# controller_pcb.net
KiCad netlist of a schematic drawn in EAGLE
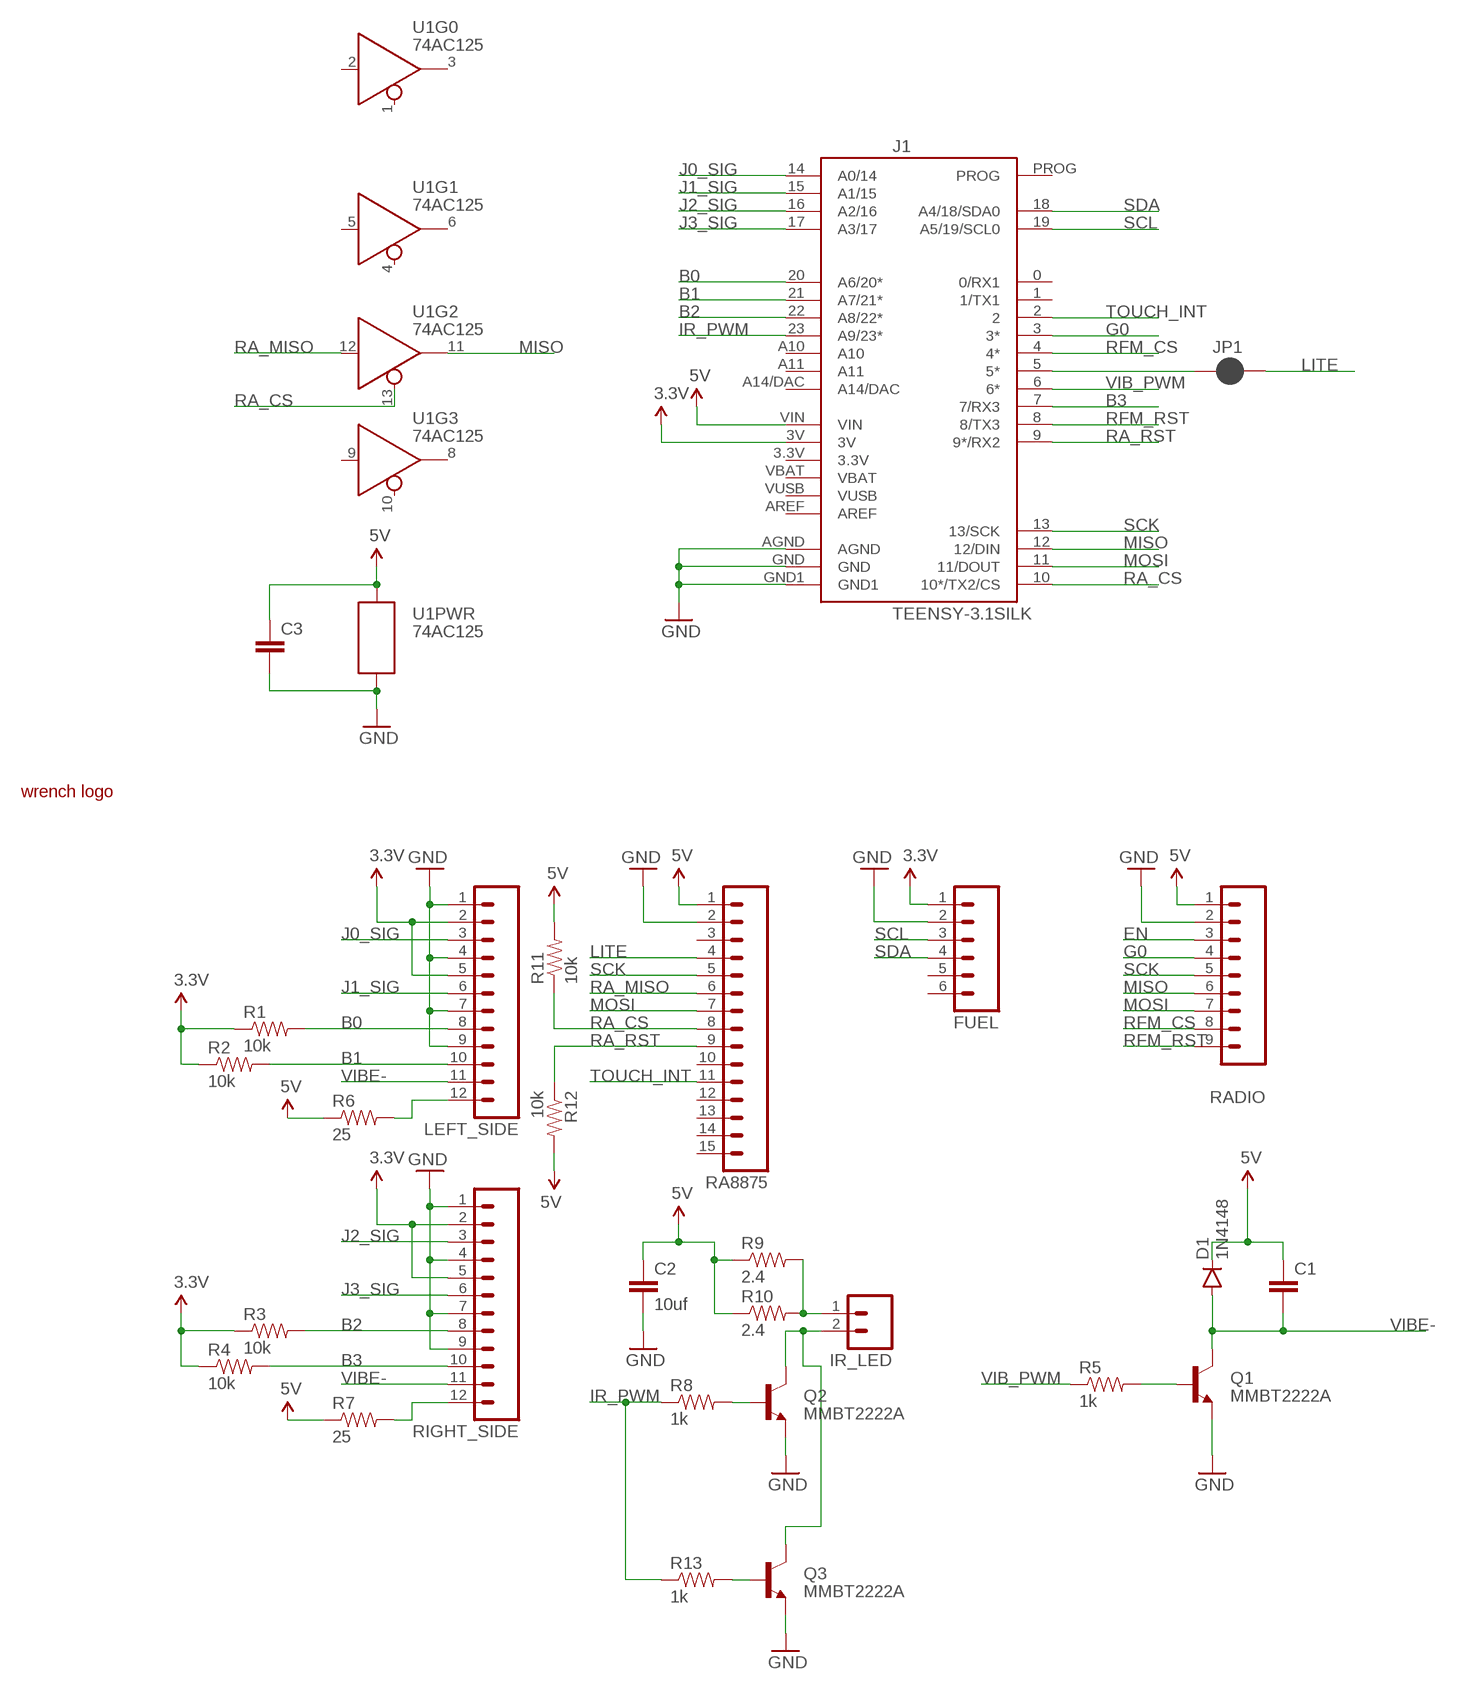
[diagram p0: schematic, sheet 1]

(export (version "E")
  (design (tool "Eeschema 10.0.6"))
  (components
    (comp (ref "C1")
      (value "CAP0805")
      (footprint "eagle-import:0805")
      (libsource (lib "eagle-import") (part "CAP0805"))
    )
    (comp (ref "C2")
      (value "10uf")
      (footprint "eagle-import:1206")
      (libsource (lib "eagle-import") (part "CAP1206"))
    )
    (comp (ref "C3")
      (value "CAP0805")
      (footprint "eagle-import:0805")
      (libsource (lib "eagle-import") (part "CAP0805"))
    )
    (comp (ref "D1")
      (value "1N4148")
      (footprint "eagle-import:DIODE-1N4148")
      (libsource (lib "eagle-import") (part "DIODE1N4148"))
    )
    (comp (ref "FUEL")
      (value "M06LOCK_LONGPADS")
      (footprint "eagle-import:1X06_LOCK_LONGPADS")
      (libsource (lib "eagle-import") (part "M06LOCK_LONGPADS"))
    )
    (comp (ref "IR_LED")
      (value "M02PTH3")
      (footprint "eagle-import:1X02_LONGPADS")
      (libsource (lib "eagle-import") (part "M02PTH3"))
    )
    (comp (ref "J1")
      (value "TEENSY-3.1SILK")
      (footprint "eagle-import:TEENSY-3.1")
      (libsource (lib "eagle-import") (part "TEENSY-3.1SILK"))
    )
    (comp (ref "JP1")
      (value "JUMPER-PAD-2-NC_BY_PASTE")
      (footprint "eagle-import:PAD-JUMPER-2-NC_BY_PASTE_YES_SILK")
      (libsource (lib "eagle-import") (part "JUMPER-PAD-2-NC_BY_PASTE"))
    )
    (comp (ref "LEFT_SIDE")
      (value "M12LONGPADS")
      (footprint "eagle-import:1X12_LONGPADS")
      (libsource (lib "eagle-import") (part "M12LONGPADS"))
    )
    (comp (ref "Q1")
      (value "MMBT2222A")
      (footprint "eagle-import:SOT23-3")
      (libsource (lib "eagle-import") (part "TRANSISTOR_NPNMMBT2222A"))
    )
    (comp (ref "Q2")
      (value "MMBT2222A")
      (footprint "eagle-import:SOT23-3")
      (libsource (lib "eagle-import") (part "TRANSISTOR_NPNMMBT2222A"))
    )
    (comp (ref "Q3")
      (value "MMBT2222A")
      (footprint "eagle-import:SOT23-3")
      (libsource (lib "eagle-import") (part "TRANSISTOR_NPNMMBT2222A"))
    )
    (comp (ref "R1")
      (value "10k")
      (footprint "eagle-import:0805")
      (libsource (lib "eagle-import") (part "RESISTOR0805-RES"))
    )
    (comp (ref "R2")
      (value "10k")
      (footprint "eagle-import:0805")
      (libsource (lib "eagle-import") (part "RESISTOR0805-RES"))
    )
    (comp (ref "R3")
      (value "10k")
      (footprint "eagle-import:0805")
      (libsource (lib "eagle-import") (part "RESISTOR0805-RES"))
    )
    (comp (ref "R4")
      (value "10k")
      (footprint "eagle-import:0805")
      (libsource (lib "eagle-import") (part "RESISTOR0805-RES"))
    )
    (comp (ref "R5")
      (value "1k")
      (footprint "eagle-import:0805")
      (libsource (lib "eagle-import") (part "RESISTOR0805-RES"))
    )
    (comp (ref "R6")
      (value "25")
      (footprint "eagle-import:0805")
      (libsource (lib "eagle-import") (part "RESISTOR0805-RES"))
    )
    (comp (ref "R7")
      (value "25")
      (footprint "eagle-import:0805")
      (libsource (lib "eagle-import") (part "RESISTOR0805-RES"))
    )
    (comp (ref "R8")
      (value "1k")
      (footprint "eagle-import:0805")
      (libsource (lib "eagle-import") (part "RESISTOR0805-RES"))
    )
    (comp (ref "R9")
      (value "2.4")
      (footprint "eagle-import:AXIAL-0.5")
      (libsource (lib "eagle-import") (part "RESISTORPTH-1/2W"))
    )
    (comp (ref "R10")
      (value "2.4")
      (footprint "eagle-import:AXIAL-0.5")
      (libsource (lib "eagle-import") (part "RESISTORPTH-1/2W"))
    )
    (comp (ref "R11")
      (value "10k")
      (footprint "eagle-import:0805")
      (libsource (lib "eagle-import") (part "RESISTOR0805-RES"))
    )
    (comp (ref "R12")
      (value "10k")
      (footprint "eagle-import:0805")
      (libsource (lib "eagle-import") (part "RESISTOR0805-RES"))
    )
    (comp (ref "R13")
      (value "1k")
      (footprint "eagle-import:0805")
      (libsource (lib "eagle-import") (part "RESISTOR0805-RES"))
    )
    (comp (ref "RA8875")
      (value "M15LOCK_LONGPADS")
      (footprint "eagle-import:1X15_LOCK_LONGPADS")
      (libsource (lib "eagle-import") (part "M15LOCK_LONGPADS"))
    )
    (comp (ref "RADIO")
      (value "M09LOCK-LONGPADS")
      (footprint "eagle-import:1X09_LOCK_LONGPADS")
      (libsource (lib "eagle-import") (part "M09LOCK-LONGPADS"))
    )
    (comp (ref "RIGHT_SIDE")
      (value "M12LONGPADS")
      (footprint "eagle-import:1X12_LONGPADS")
      (libsource (lib "eagle-import") (part "M12LONGPADS"))
    )
    (comp (ref "U$1")
      (value "SMALL")
      (footprint "eagle-import:WRENCHLOGO")
      (libsource (lib "eagle-import") (part "SMALL"))
    )
    (comp (ref "U1")
      (value "74AC125")
      (footprint "eagle-import:SO14")
      (libsource (lib "eagle-import") (part "74125AC125DG"))
    )
  )
  (nets
    (net (code "1") (name "/B0") (class "Default")
      (node (ref "J1") (pin "20") (pinfunction "A6/20*_20") (pintype "bidirectional"))
      (node (ref "LEFT_SIDE") (pin "8") (pinfunction "8_8") (pintype "passive"))
      (node (ref "R1") (pin "2") (pinfunction "2_2") (pintype "passive"))
    )
    (net (code "2") (name "/B1") (class "Default")
      (node (ref "J1") (pin "21") (pinfunction "A7/21*_21") (pintype "bidirectional"))
      (node (ref "LEFT_SIDE") (pin "10") (pinfunction "10_10") (pintype "passive"))
      (node (ref "R2") (pin "2") (pinfunction "2_2") (pintype "passive"))
    )
    (net (code "3") (name "/B2") (class "Default")
      (node (ref "J1") (pin "22") (pinfunction "A8/22*_22") (pintype "bidirectional"))
      (node (ref "R3") (pin "2") (pinfunction "2_2") (pintype "passive"))
      (node (ref "RIGHT_SIDE") (pin "8") (pinfunction "8_8") (pintype "passive"))
    )
    (net (code "4") (name "/B3") (class "Default")
      (node (ref "J1") (pin "7") (pinfunction "7/RX3_7") (pintype "bidirectional"))
      (node (ref "R4") (pin "2") (pinfunction "2_2") (pintype "passive"))
      (node (ref "RIGHT_SIDE") (pin "10") (pinfunction "10_10") (pintype "passive"))
    )
    (net (code "5") (name "/EN") (class "Default")
      (node (ref "RADIO") (pin "3") (pinfunction "3_3") (pintype "passive"))
    )
    (net (code "6") (name "/G0") (class "Default")
      (node (ref "J1") (pin "3") (pinfunction "3*_3") (pintype "bidirectional"))
      (node (ref "RADIO") (pin "4") (pinfunction "4_4") (pintype "passive"))
    )
    (net (code "7") (name "/IR_PWM") (class "Default")
      (node (ref "J1") (pin "23") (pinfunction "A9/23*_23") (pintype "bidirectional"))
      (node (ref "R13") (pin "1") (pinfunction "1_1") (pintype "passive"))
      (node (ref "R8") (pin "1") (pinfunction "1_1") (pintype "passive"))
    )
    (net (code "8") (name "/J0_SIG") (class "Default")
      (node (ref "J1") (pin "14") (pinfunction "A0/14_14") (pintype "bidirectional"))
      (node (ref "LEFT_SIDE") (pin "3") (pinfunction "3_3") (pintype "passive"))
    )
    (net (code "9") (name "/J1_SIG") (class "Default")
      (node (ref "J1") (pin "15") (pinfunction "A1/15_15") (pintype "bidirectional"))
      (node (ref "LEFT_SIDE") (pin "6") (pinfunction "6_6") (pintype "passive"))
    )
    (net (code "10") (name "/J2_SIG") (class "Default")
      (node (ref "J1") (pin "16") (pinfunction "A2/16_16") (pintype "bidirectional"))
      (node (ref "RIGHT_SIDE") (pin "3") (pinfunction "3_3") (pintype "passive"))
    )
    (net (code "11") (name "/J3_SIG") (class "Default")
      (node (ref "J1") (pin "17") (pinfunction "A3/17_17") (pintype "bidirectional"))
      (node (ref "RIGHT_SIDE") (pin "6") (pinfunction "6_6") (pintype "passive"))
    )
    (net (code "12") (name "/LITE") (class "Default")
      (node (ref "JP1") (pin "2") (pinfunction "2_2") (pintype "passive"))
      (node (ref "RA8875") (pin "4") (pinfunction "4_4") (pintype "passive"))
    )
    (net (code "13") (name "/MISO") (class "Default")
      (node (ref "J1") (pin "12") (pinfunction "12/DIN_12") (pintype "bidirectional"))
      (node (ref "RADIO") (pin "6") (pinfunction "6_6") (pintype "passive"))
      (node (ref "U1") (pin "11") (pinfunction "Q_11") (pintype "bidirectional"))
    )
    (net (code "14") (name "/MOSI") (class "Default")
      (node (ref "J1") (pin "11") (pinfunction "11/DOUT_11") (pintype "bidirectional"))
      (node (ref "RA8875") (pin "7") (pinfunction "7_7") (pintype "passive"))
      (node (ref "RADIO") (pin "7") (pinfunction "7_7") (pintype "passive"))
    )
    (net (code "15") (name "/RA_CS") (class "Default")
      (node (ref "J1") (pin "10") (pinfunction "10*/TX2/CS_10") (pintype "bidirectional"))
      (node (ref "R11") (pin "1") (pinfunction "1_1") (pintype "passive"))
      (node (ref "RA8875") (pin "8") (pinfunction "8_8") (pintype "passive"))
      (node (ref "U1") (pin "13") (pinfunction "~{EN}_13") (pintype "bidirectional"))
    )
    (net (code "16") (name "/RA_MISO") (class "Default")
      (node (ref "RA8875") (pin "6") (pinfunction "6_6") (pintype "passive"))
      (node (ref "U1") (pin "12") (pinfunction "D_12") (pintype "bidirectional"))
    )
    (net (code "17") (name "/RA_RST") (class "Default")
      (node (ref "J1") (pin "9") (pinfunction "9*/RX2_9") (pintype "bidirectional"))
      (node (ref "R12") (pin "1") (pinfunction "1_1") (pintype "passive"))
      (node (ref "RA8875") (pin "9") (pinfunction "9_9") (pintype "passive"))
    )
    (net (code "18") (name "/RFM_CS") (class "Default")
      (node (ref "J1") (pin "4") (pinfunction "4*_4") (pintype "bidirectional"))
      (node (ref "RADIO") (pin "8") (pinfunction "8_8") (pintype "passive"))
    )
    (net (code "19") (name "/RFM_RST") (class "Default")
      (node (ref "J1") (pin "8") (pinfunction "8/TX3_8") (pintype "bidirectional"))
      (node (ref "RADIO") (pin "9") (pinfunction "9_9") (pintype "passive"))
    )
    (net (code "20") (name "/SCK") (class "Default")
      (node (ref "J1") (pin "13") (pinfunction "13/SCK_13") (pintype "bidirectional"))
      (node (ref "RA8875") (pin "5") (pinfunction "5_5") (pintype "passive"))
      (node (ref "RADIO") (pin "5") (pinfunction "5_5") (pintype "passive"))
    )
    (net (code "21") (name "/SCL") (class "Default")
      (node (ref "FUEL") (pin "3") (pinfunction "3_3") (pintype "passive"))
      (node (ref "J1") (pin "19") (pinfunction "A5/19/SCL0_19") (pintype "bidirectional"))
    )
    (net (code "22") (name "/SDA") (class "Default")
      (node (ref "FUEL") (pin "4") (pinfunction "4_4") (pintype "passive"))
      (node (ref "J1") (pin "18") (pinfunction "A4/18/SDA0_18") (pintype "bidirectional"))
    )
    (net (code "23") (name "/TOUCH_INT") (class "Default")
      (node (ref "J1") (pin "2") (pinfunction "2_2") (pintype "bidirectional"))
      (node (ref "RA8875") (pin "11") (pinfunction "11_11") (pintype "passive"))
    )
    (net (code "24") (name "/VIBE-") (class "Default")
      (node (ref "C1") (pin "2") (pinfunction "2_2") (pintype "passive"))
      (node (ref "D1") (pin "A") (pinfunction "A_A") (pintype "passive"))
      (node (ref "LEFT_SIDE") (pin "11") (pinfunction "11_11") (pintype "passive"))
      (node (ref "Q1") (pin "3") (pinfunction "C_3") (pintype "passive"))
      (node (ref "RIGHT_SIDE") (pin "11") (pinfunction "11_11") (pintype "passive"))
    )
    (net (code "25") (name "/VIB_PWM") (class "Default")
      (node (ref "J1") (pin "6") (pinfunction "6*_6") (pintype "bidirectional"))
      (node (ref "R5") (pin "1") (pinfunction "1_1") (pintype "passive"))
    )
    (net (code "26") (name "3.3V") (class "Default")
      (node (ref "FUEL") (pin "1") (pinfunction "1_1") (pintype "passive"))
      (node (ref "J1") (pin "3V") (pinfunction "3V_3V") (pintype "bidirectional"))
      (node (ref "LEFT_SIDE") (pin "2") (pinfunction "2_2") (pintype "passive"))
      (node (ref "LEFT_SIDE") (pin "5") (pinfunction "5_5") (pintype "passive"))
      (node (ref "R1") (pin "1") (pinfunction "1_1") (pintype "passive"))
      (node (ref "R2") (pin "1") (pinfunction "1_1") (pintype "passive"))
      (node (ref "R3") (pin "1") (pinfunction "1_1") (pintype "passive"))
      (node (ref "R4") (pin "1") (pinfunction "1_1") (pintype "passive"))
      (node (ref "RIGHT_SIDE") (pin "2") (pinfunction "2_2") (pintype "passive"))
      (node (ref "RIGHT_SIDE") (pin "5") (pinfunction "5_5") (pintype "passive"))
    )
    (net (code "27") (name "5V") (class "Default")
      (node (ref "C1") (pin "1") (pinfunction "1_1") (pintype "passive"))
      (node (ref "C2") (pin "1") (pinfunction "1_1") (pintype "passive"))
      (node (ref "C3") (pin "1") (pinfunction "1_1") (pintype "passive"))
      (node (ref "D1") (pin "C") (pinfunction "C_C") (pintype "passive"))
      (node (ref "J1") (pin "VIN") (pinfunction "VIN_VIN") (pintype "bidirectional"))
      (node (ref "R10") (pin "P$1") (pinfunction "1_P$1") (pintype "passive"))
      (node (ref "R11") (pin "2") (pinfunction "2_2") (pintype "passive"))
      (node (ref "R12") (pin "2") (pinfunction "2_2") (pintype "passive"))
      (node (ref "R6") (pin "1") (pinfunction "1_1") (pintype "passive"))
      (node (ref "R7") (pin "1") (pinfunction "1_1") (pintype "passive"))
      (node (ref "R9") (pin "P$1") (pinfunction "1_P$1") (pintype "passive"))
      (node (ref "RA8875") (pin "1") (pinfunction "1_1") (pintype "passive"))
      (node (ref "RADIO") (pin "1") (pinfunction "1_1") (pintype "passive"))
      (node (ref "U1") (pin "14") (pinfunction "P$V+_14") (pintype "bidirectional"))
    )
    (net (code "28") (name "GND") (class "Default")
      (node (ref "C2") (pin "2") (pinfunction "2_2") (pintype "passive"))
      (node (ref "C3") (pin "2") (pinfunction "2_2") (pintype "passive"))
      (node (ref "FUEL") (pin "2") (pinfunction "2_2") (pintype "passive"))
      (node (ref "J1") (pin "AGND") (pinfunction "AGND_AGND") (pintype "bidirectional"))
      (node (ref "J1") (pin "GND") (pinfunction "GND_GND") (pintype "bidirectional"))
      (node (ref "J1") (pin "GND1") (pinfunction "GND1_GND1") (pintype "bidirectional"))
      (node (ref "LEFT_SIDE") (pin "1") (pinfunction "1_1") (pintype "passive"))
      (node (ref "LEFT_SIDE") (pin "4") (pinfunction "4_4") (pintype "passive"))
      (node (ref "LEFT_SIDE") (pin "7") (pinfunction "7_7") (pintype "passive"))
      (node (ref "LEFT_SIDE") (pin "9") (pinfunction "9_9") (pintype "passive"))
      (node (ref "Q1") (pin "2") (pinfunction "E_2") (pintype "passive"))
      (node (ref "Q2") (pin "2") (pinfunction "E_2") (pintype "passive"))
      (node (ref "Q3") (pin "2") (pinfunction "E_2") (pintype "passive"))
      (node (ref "RA8875") (pin "2") (pinfunction "2_2") (pintype "passive"))
      (node (ref "RADIO") (pin "2") (pinfunction "2_2") (pintype "passive"))
      (node (ref "RIGHT_SIDE") (pin "1") (pinfunction "1_1") (pintype "passive"))
      (node (ref "RIGHT_SIDE") (pin "4") (pinfunction "4_4") (pintype "passive"))
      (node (ref "RIGHT_SIDE") (pin "7") (pinfunction "7_7") (pintype "passive"))
      (node (ref "RIGHT_SIDE") (pin "9") (pinfunction "9_9") (pintype "passive"))
      (node (ref "U1") (pin "7") (pinfunction "P$V-_7") (pintype "bidirectional"))
    )
    (net (code "29") (name "Net-(J1-5*)") (class "Default")
      (node (ref "J1") (pin "5") (pinfunction "5*_5") (pintype "bidirectional"))
      (node (ref "JP1") (pin "1") (pinfunction "1_1") (pintype "passive"))
    )
    (net (code "30") (name "Net-(LEFT_SIDE-Pad12)") (class "Default")
      (node (ref "LEFT_SIDE") (pin "12") (pinfunction "12_12") (pintype "passive"))
      (node (ref "R6") (pin "2") (pinfunction "2_2") (pintype "passive"))
    )
    (net (code "31") (name "Net-(Q1-B)") (class "Default")
      (node (ref "Q1") (pin "1") (pinfunction "B_1") (pintype "passive"))
      (node (ref "R5") (pin "2") (pinfunction "2_2") (pintype "passive"))
    )
    (net (code "32") (name "Net-(Q2-B)") (class "Default")
      (node (ref "Q2") (pin "1") (pinfunction "B_1") (pintype "passive"))
      (node (ref "R8") (pin "2") (pinfunction "2_2") (pintype "passive"))
    )
    (net (code "33") (name "Net-(Q2-C)") (class "Default")
      (node (ref "IR_LED") (pin "2") (pinfunction "2_2") (pintype "passive"))
      (node (ref "Q2") (pin "3") (pinfunction "C_3") (pintype "passive"))
      (node (ref "Q3") (pin "3") (pinfunction "C_3") (pintype "passive"))
    )
    (net (code "34") (name "Net-(Q3-B)") (class "Default")
      (node (ref "Q3") (pin "1") (pinfunction "B_1") (pintype "passive"))
      (node (ref "R13") (pin "2") (pinfunction "2_2") (pintype "passive"))
    )
    (net (code "35") (name "Net-(R7-Pad2)") (class "Default")
      (node (ref "R7") (pin "2") (pinfunction "2_2") (pintype "passive"))
      (node (ref "RIGHT_SIDE") (pin "12") (pinfunction "12_12") (pintype "passive"))
    )
    (net (code "36") (name "Net-(R10-2)") (class "Default")
      (node (ref "IR_LED") (pin "1") (pinfunction "1_1") (pintype "passive"))
      (node (ref "R10") (pin "P$2") (pinfunction "2_P$2") (pintype "passive"))
      (node (ref "R9") (pin "P$2") (pinfunction "2_P$2") (pintype "passive"))
    )
    (net (code "37") (name "unconnected-(FUEL-Pad5)") (class "Default")
      (node (ref "FUEL") (pin "5") (pinfunction "5_5") (pintype "passive"))
    )
    (net (code "38") (name "unconnected-(FUEL-Pad6)") (class "Default")
      (node (ref "FUEL") (pin "6") (pinfunction "6_6") (pintype "passive"))
    )
    (net (code "39") (name "unconnected-(J1-0{slash}RX1-Pad0)") (class "Default")
      (node (ref "J1") (pin "0") (pinfunction "0/RX1_0") (pintype "bidirectional"))
    )
    (net (code "40") (name "unconnected-(J1-1{slash}TX1-Pad1)") (class "Default")
      (node (ref "J1") (pin "1") (pinfunction "1/TX1_1") (pintype "bidirectional"))
    )
    (net (code "41") (name "unconnected-(J1-Pad3.3V)") (class "Default")
      (node (ref "J1") (pin "3.3V") (pinfunction "3.3V_3.3V") (pintype "bidirectional"))
    )
    (net (code "42") (name "unconnected-(J1-PadA10)") (class "Default")
      (node (ref "J1") (pin "A10") (pinfunction "A10_A10") (pintype "bidirectional"))
    )
    (net (code "43") (name "unconnected-(J1-PadA11)") (class "Default")
      (node (ref "J1") (pin "A11") (pinfunction "A11_A11") (pintype "bidirectional"))
    )
    (net (code "44") (name "unconnected-(J1-PadA14{slash}DAC)") (class "Default")
      (node (ref "J1") (pin "A14/DAC") (pinfunction "A14/DAC_A14/DAC") (pintype "bidirectional"))
    )
    (net (code "45") (name "unconnected-(J1-PadAREF)") (class "Default")
      (node (ref "J1") (pin "AREF") (pinfunction "AREF_AREF") (pintype "bidirectional"))
    )
    (net (code "46") (name "unconnected-(J1-PadPROG)") (class "Default")
      (node (ref "J1") (pin "PROG") (pinfunction "PROG_PROG") (pintype "bidirectional"))
    )
    (net (code "47") (name "unconnected-(J1-PadVBAT)") (class "Default")
      (node (ref "J1") (pin "VBAT") (pinfunction "VBAT_VBAT") (pintype "bidirectional"))
    )
    (net (code "48") (name "unconnected-(J1-PadVUSB)") (class "Default")
      (node (ref "J1") (pin "VUSB") (pinfunction "VUSB_VUSB") (pintype "bidirectional"))
    )
    (net (code "49") (name "unconnected-(RA8875-Pad3)") (class "Default")
      (node (ref "RA8875") (pin "3") (pinfunction "3_3") (pintype "passive"))
    )
    (net (code "50") (name "unconnected-(RA8875-Pad10)") (class "Default")
      (node (ref "RA8875") (pin "10") (pinfunction "10_10") (pintype "passive"))
    )
    (net (code "51") (name "unconnected-(RA8875-Pad12)") (class "Default")
      (node (ref "RA8875") (pin "12") (pinfunction "12_12") (pintype "passive"))
    )
    (net (code "52") (name "unconnected-(RA8875-Pad13)") (class "Default")
      (node (ref "RA8875") (pin "13") (pinfunction "13_13") (pintype "passive"))
    )
    (net (code "53") (name "unconnected-(RA8875-Pad14)") (class "Default")
      (node (ref "RA8875") (pin "14") (pinfunction "14_14") (pintype "passive"))
    )
    (net (code "54") (name "unconnected-(RA8875-Pad15)") (class "Default")
      (node (ref "RA8875") (pin "15") (pinfunction "15_15") (pintype "passive"))
    )
    (net (code "55") (name "unconnected-(U1A-D-Pad2)") (class "Default")
      (node (ref "U1") (pin "2") (pinfunction "D_2") (pintype "bidirectional"))
    )
    (net (code "56") (name "unconnected-(U1A-Q-Pad3)") (class "Default")
      (node (ref "U1") (pin "3") (pinfunction "Q_3") (pintype "bidirectional"))
    )
    (net (code "57") (name "unconnected-(U1A-~{EN}-Pad1)") (class "Default")
      (node (ref "U1") (pin "1") (pinfunction "~{EN}_1") (pintype "bidirectional"))
    )
    (net (code "58") (name "unconnected-(U1B-D-Pad5)") (class "Default")
      (node (ref "U1") (pin "5") (pinfunction "D_5") (pintype "bidirectional"))
    )
    (net (code "59") (name "unconnected-(U1B-Q-Pad6)") (class "Default")
      (node (ref "U1") (pin "6") (pinfunction "Q_6") (pintype "bidirectional"))
    )
    (net (code "60") (name "unconnected-(U1B-~{EN}-Pad4)") (class "Default")
      (node (ref "U1") (pin "4") (pinfunction "~{EN}_4") (pintype "bidirectional"))
    )
    (net (code "61") (name "unconnected-(U1D-D-Pad9)") (class "Default")
      (node (ref "U1") (pin "9") (pinfunction "D_9") (pintype "bidirectional"))
    )
    (net (code "62") (name "unconnected-(U1D-Q-Pad8)") (class "Default")
      (node (ref "U1") (pin "8") (pinfunction "Q_8") (pintype "bidirectional"))
    )
    (net (code "63") (name "unconnected-(U1D-~{EN}-Pad10)") (class "Default")
      (node (ref "U1") (pin "10") (pinfunction "~{EN}_10") (pintype "bidirectional"))
    )
  )
)
